# MCU.net
KiCad netlist of a schematic drawn in Altium Designer
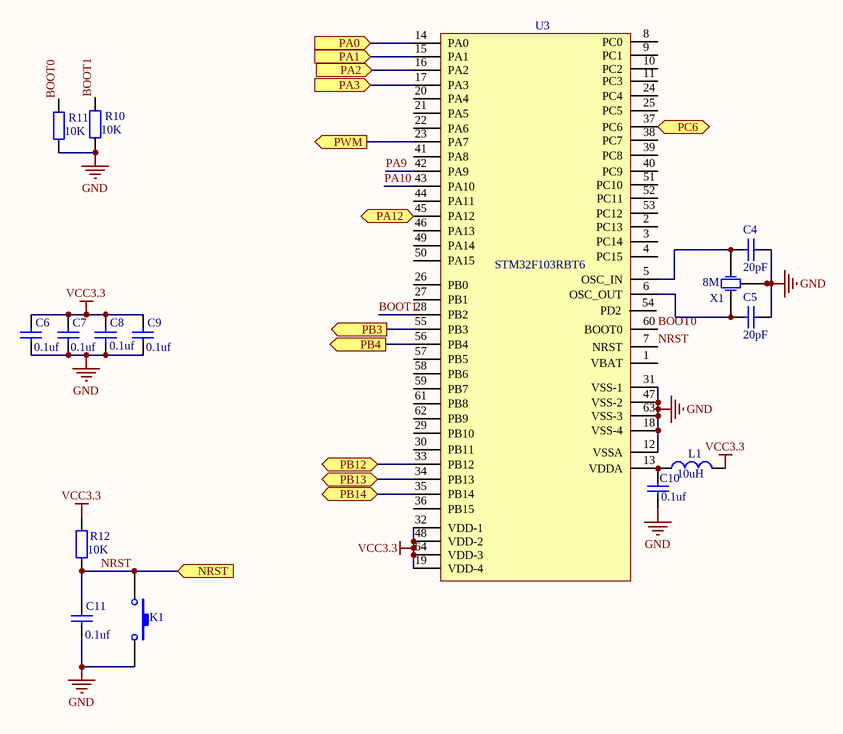
[diagram p0: MCU.SchDoc]

(export (version "E")
  (design (tool "Eeschema 10.0.6"))
  (components
    (comp (ref "C4")
      (value "20pF")
      (footprint "0603")
      (fields (field (name "Comment") "Capacitor-0805"))
      (libsource (lib "原理图库") (part "Capacitor-0805"))
    )
    (comp (ref "C5")
      (value "20pF")
      (footprint "0603")
      (fields (field (name "Comment") "Capacitor-0805"))
      (libsource (lib "原理图库") (part "Capacitor-0805"))
    )
    (comp (ref "C6")
      (value "0.1uf")
      (footprint "0603")
      (fields (field (name "Comment") "Capacitor-0603"))
      (libsource (lib "原理图库") (part "Capacitor-0603"))
    )
    (comp (ref "C7")
      (value "0.1uf")
      (footprint "0603")
      (fields (field (name "Comment") "Capacitor-0603"))
      (libsource (lib "原理图库") (part "Capacitor-0603"))
    )
    (comp (ref "C8")
      (value "0.1uf")
      (footprint "0603")
      (fields (field (name "Comment") "Capacitor-0603"))
      (libsource (lib "原理图库") (part "Capacitor-0603"))
    )
    (comp (ref "C9")
      (value "0.1uf")
      (footprint "0603")
      (fields (field (name "Comment") "Capacitor-0603"))
      (libsource (lib "原理图库") (part "Capacitor-0603"))
    )
    (comp (ref "C10")
      (value "0.1uf")
      (footprint "0603")
      (fields (field (name "Comment") "Capacitor-0603"))
      (libsource (lib "原理图库") (part "Capacitor-0603"))
    )
    (comp (ref "C11")
      (value "0.1uf")
      (footprint "0603")
      (fields (field (name "Comment") "Capacitor-0603"))
      (libsource (lib "原理图库") (part "Capacitor-0603"))
    )
    (comp (ref "K1") (value "按键") (footprint "mini按键") (libsource (lib "原理图库") (part "按键")))
    (comp (ref "L1")
      (value "10uH")
      (footprint "0805")
      (fields (field (name "Comment") "Inductor"))
      (libsource (lib "原理图库") (part "Inductor"))
    )
    (comp (ref "R10")
      (value "10K")
      (footprint "0603")
      (fields (field (name "Comment") "Resistor-0603"))
      (libsource (lib "原理图库") (part "Resistor-0603"))
    )
    (comp (ref "R11")
      (value "10K")
      (footprint "0603")
      (fields (field (name "Comment") "Resistor-0603"))
      (libsource (lib "原理图库") (part "Resistor-0603"))
    )
    (comp (ref "R12")
      (value "10K")
      (footprint "0603")
      (fields (field (name "Comment") "Resistor-0603"))
      (libsource (lib "原理图库") (part "Resistor-0603"))
    )
    (comp (ref "U3")
      (value "STM32F103RBT6")
      (footprint "STM32F103RBT6")
      (fields (field (name "NAME") "STM32F103RBT6"))
      (libsource (lib "原理图库") (part "STM32F103RBT6"))
    )
    (comp (ref "X1")
      (value "8M")
      (footprint "3225无源晶振")
      (fields (field (name "Comment") "3225无源晶振"))
      (libsource (lib "原理图库") (part "3225无源晶振"))
    )
  )
  (nets
    (net (code "1") (name "/BOOT0") (class "Default")
      (node (ref "R11") (pin "2") (pinfunction "2_2") (pintype "passive"))
      (node (ref "U3") (pin "60") (pinfunction "BOOT0_60") (pintype "passive"))
    )
    (net (code "2") (name "/BOOT1") (class "Default")
      (node (ref "R10") (pin "2") (pinfunction "2_2") (pintype "passive"))
      (node (ref "U3") (pin "28") (pinfunction "PB2_28") (pintype "passive"))
    )
    (net (code "3") (name "/NRST") (class "Default")
      (node (ref "C11") (pin "2") (pinfunction "2_2") (pintype "passive"))
      (node (ref "K1") (pin "1") (pinfunction "1_1") (pintype "passive"))
      (node (ref "R12") (pin "1") (pinfunction "1_1") (pintype "passive"))
      (node (ref "U3") (pin "7") (pinfunction "NRST_7") (pintype "passive"))
    )
    (net (code "4") (name "/PA0") (class "Default")
      (node (ref "U3") (pin "14") (pinfunction "PA0_14") (pintype "passive"))
    )
    (net (code "5") (name "/PA1") (class "Default")
      (node (ref "U3") (pin "15") (pinfunction "PA1_15") (pintype "passive"))
    )
    (net (code "6") (name "/PA2") (class "Default")
      (node (ref "U3") (pin "16") (pinfunction "PA2_16") (pintype "passive"))
    )
    (net (code "7") (name "/PA3") (class "Default")
      (node (ref "U3") (pin "17") (pinfunction "PA3_17") (pintype "passive"))
    )
    (net (code "8") (name "/PA9") (class "Default")
      (node (ref "U3") (pin "42") (pinfunction "PA9_42") (pintype "passive"))
    )
    (net (code "9") (name "/PA10") (class "Default")
      (node (ref "U3") (pin "43") (pinfunction "PA10_43") (pintype "passive"))
    )
    (net (code "10") (name "/PA12") (class "Default")
      (node (ref "U3") (pin "45") (pinfunction "PA12_45") (pintype "passive"))
    )
    (net (code "11") (name "/PB3") (class "Default")
      (node (ref "U3") (pin "55") (pinfunction "PB3_55") (pintype "passive"))
    )
    (net (code "12") (name "/PB4") (class "Default")
      (node (ref "U3") (pin "56") (pinfunction "PB4_56") (pintype "passive"))
    )
    (net (code "13") (name "/PB12") (class "Default")
      (node (ref "U3") (pin "33") (pinfunction "PB12_33") (pintype "passive"))
    )
    (net (code "14") (name "/PB13") (class "Default")
      (node (ref "U3") (pin "34") (pinfunction "PB13_34") (pintype "passive"))
    )
    (net (code "15") (name "/PB14") (class "Default")
      (node (ref "U3") (pin "35") (pinfunction "PB14_35") (pintype "passive"))
    )
    (net (code "16") (name "/PC6") (class "Default")
      (node (ref "U3") (pin "37") (pinfunction "PC6_37") (pintype "passive"))
    )
    (net (code "17") (name "/PWM") (class "Default")
      (node (ref "U3") (pin "23") (pinfunction "PA7_23") (pintype "passive"))
    )
    (net (code "18") (name "GND") (class "Default")
      (node (ref "C10") (pin "1") (pinfunction "1_1") (pintype "passive"))
      (node (ref "C11") (pin "1") (pinfunction "1_1") (pintype "passive"))
      (node (ref "C4") (pin "1") (pinfunction "1_1") (pintype "passive"))
      (node (ref "C5") (pin "1") (pinfunction "1_1") (pintype "passive"))
      (node (ref "C6") (pin "1") (pinfunction "1_1") (pintype "passive"))
      (node (ref "C7") (pin "1") (pinfunction "1_1") (pintype "passive"))
      (node (ref "C8") (pin "1") (pinfunction "1_1") (pintype "passive"))
      (node (ref "C9") (pin "1") (pinfunction "1_1") (pintype "passive"))
      (node (ref "K1") (pin "2") (pinfunction "2_2") (pintype "passive"))
      (node (ref "R10") (pin "1") (pinfunction "1_1") (pintype "passive"))
      (node (ref "R11") (pin "1") (pinfunction "1_1") (pintype "passive"))
      (node (ref "U3") (pin "12") (pinfunction "VSSA_12") (pintype "passive"))
      (node (ref "U3") (pin "18") (pinfunction "VSS-4_18") (pintype "passive"))
      (node (ref "U3") (pin "31") (pinfunction "VSS-1_31") (pintype "passive"))
      (node (ref "U3") (pin "47") (pinfunction "VSS-2_47") (pintype "passive"))
      (node (ref "U3") (pin "63") (pinfunction "VSS-3_63") (pintype "passive"))
      (node (ref "X1") (pin "2") (pinfunction "GND_2") (pintype "passive"))
      (node (ref "X1") (pin "4") (pinfunction "GND_4") (pintype "passive"))
    )
    (net (code "19") (name "Net-(U3-OSC_IN)") (class "Default")
      (node (ref "C4") (pin "2") (pinfunction "2_2") (pintype "passive"))
      (node (ref "U3") (pin "5") (pinfunction "OSC_IN_5") (pintype "passive"))
      (node (ref "X1") (pin "3") (pinfunction "OSC2_3") (pintype "passive"))
    )
    (net (code "20") (name "Net-(U3-OSC_OUT)") (class "Default")
      (node (ref "C5") (pin "2") (pinfunction "2_2") (pintype "passive"))
      (node (ref "U3") (pin "6") (pinfunction "OSC_OUT_6") (pintype "passive"))
      (node (ref "X1") (pin "1") (pinfunction "OSC1_1") (pintype "passive"))
    )
    (net (code "21") (name "Net-(U3-VDDA)") (class "Default")
      (node (ref "C10") (pin "2") (pinfunction "2_2") (pintype "passive"))
      (node (ref "L1") (pin "1") (pinfunction "1_1") (pintype "passive"))
      (node (ref "U3") (pin "13") (pinfunction "VDDA_13") (pintype "passive"))
    )
    (net (code "22") (name "VCC3.3") (class "Default")
      (node (ref "C6") (pin "2") (pinfunction "2_2") (pintype "passive"))
      (node (ref "C7") (pin "2") (pinfunction "2_2") (pintype "passive"))
      (node (ref "C8") (pin "2") (pinfunction "2_2") (pintype "passive"))
      (node (ref "C9") (pin "2") (pinfunction "2_2") (pintype "passive"))
      (node (ref "L1") (pin "2") (pinfunction "2_2") (pintype "passive"))
      (node (ref "R12") (pin "2") (pinfunction "2_2") (pintype "passive"))
      (node (ref "U3") (pin "19") (pinfunction "VDD-4_19") (pintype "passive"))
      (node (ref "U3") (pin "32") (pinfunction "VDD-1_32") (pintype "passive"))
      (node (ref "U3") (pin "48") (pinfunction "VDD-2_48") (pintype "passive"))
      (node (ref "U3") (pin "64") (pinfunction "VDD-3_64") (pintype "passive"))
    )
    (net (code "23") (name "unconnected-(U3-PA4-Pad20)") (class "Default")
      (node (ref "U3") (pin "20") (pinfunction "PA4_20") (pintype "passive"))
    )
    (net (code "24") (name "unconnected-(U3-PA5-Pad21)") (class "Default")
      (node (ref "U3") (pin "21") (pinfunction "PA5_21") (pintype "passive"))
    )
    (net (code "25") (name "unconnected-(U3-PA6-Pad22)") (class "Default")
      (node (ref "U3") (pin "22") (pinfunction "PA6_22") (pintype "passive"))
    )
    (net (code "26") (name "unconnected-(U3-PA8-Pad41)") (class "Default")
      (node (ref "U3") (pin "41") (pinfunction "PA8_41") (pintype "passive"))
    )
    (net (code "27") (name "unconnected-(U3-PA11-Pad44)") (class "Default")
      (node (ref "U3") (pin "44") (pinfunction "PA11_44") (pintype "passive"))
    )
    (net (code "28") (name "unconnected-(U3-PA13-Pad46)") (class "Default")
      (node (ref "U3") (pin "46") (pinfunction "PA13_46") (pintype "passive"))
    )
    (net (code "29") (name "unconnected-(U3-PA14-Pad49)") (class "Default")
      (node (ref "U3") (pin "49") (pinfunction "PA14_49") (pintype "passive"))
    )
    (net (code "30") (name "unconnected-(U3-PA15-Pad50)") (class "Default")
      (node (ref "U3") (pin "50") (pinfunction "PA15_50") (pintype "passive"))
    )
    (net (code "31") (name "unconnected-(U3-PB0-Pad26)") (class "Default")
      (node (ref "U3") (pin "26") (pinfunction "PB0_26") (pintype "passive"))
    )
    (net (code "32") (name "unconnected-(U3-PB1-Pad27)") (class "Default")
      (node (ref "U3") (pin "27") (pinfunction "PB1_27") (pintype "passive"))
    )
    (net (code "33") (name "unconnected-(U3-PB5-Pad57)") (class "Default")
      (node (ref "U3") (pin "57") (pinfunction "PB5_57") (pintype "passive"))
    )
    (net (code "34") (name "unconnected-(U3-PB6-Pad58)") (class "Default")
      (node (ref "U3") (pin "58") (pinfunction "PB6_58") (pintype "passive"))
    )
    (net (code "35") (name "unconnected-(U3-PB7-Pad59)") (class "Default")
      (node (ref "U3") (pin "59") (pinfunction "PB7_59") (pintype "passive"))
    )
    (net (code "36") (name "unconnected-(U3-PB8-Pad61)") (class "Default")
      (node (ref "U3") (pin "61") (pinfunction "PB8_61") (pintype "passive"))
    )
    (net (code "37") (name "unconnected-(U3-PB9-Pad62)") (class "Default")
      (node (ref "U3") (pin "62") (pinfunction "PB9_62") (pintype "passive"))
    )
    (net (code "38") (name "unconnected-(U3-PB10-Pad29)") (class "Default")
      (node (ref "U3") (pin "29") (pinfunction "PB10_29") (pintype "passive"))
    )
    (net (code "39") (name "unconnected-(U3-PB11-Pad30)") (class "Default")
      (node (ref "U3") (pin "30") (pinfunction "PB11_30") (pintype "passive"))
    )
    (net (code "40") (name "unconnected-(U3-PB15-Pad36)") (class "Default")
      (node (ref "U3") (pin "36") (pinfunction "PB15_36") (pintype "passive"))
    )
    (net (code "41") (name "unconnected-(U3-PC0-Pad8)") (class "Default")
      (node (ref "U3") (pin "8") (pinfunction "PC0_8") (pintype "passive"))
    )
    (net (code "42") (name "unconnected-(U3-PC1-Pad9)") (class "Default")
      (node (ref "U3") (pin "9") (pinfunction "PC1_9") (pintype "passive"))
    )
    (net (code "43") (name "unconnected-(U3-PC2-Pad10)") (class "Default")
      (node (ref "U3") (pin "10") (pinfunction "PC2_10") (pintype "passive"))
    )
    (net (code "44") (name "unconnected-(U3-PC3-Pad11)") (class "Default")
      (node (ref "U3") (pin "11") (pinfunction "PC3_11") (pintype "passive"))
    )
    (net (code "45") (name "unconnected-(U3-PC4-Pad24)") (class "Default")
      (node (ref "U3") (pin "24") (pinfunction "PC4_24") (pintype "passive"))
    )
    (net (code "46") (name "unconnected-(U3-PC5-Pad25)") (class "Default")
      (node (ref "U3") (pin "25") (pinfunction "PC5_25") (pintype "passive"))
    )
    (net (code "47") (name "unconnected-(U3-PC7-Pad38)") (class "Default")
      (node (ref "U3") (pin "38") (pinfunction "PC7_38") (pintype "passive"))
    )
    (net (code "48") (name "unconnected-(U3-PC8-Pad39)") (class "Default")
      (node (ref "U3") (pin "39") (pinfunction "PC8_39") (pintype "passive"))
    )
    (net (code "49") (name "unconnected-(U3-PC9-Pad40)") (class "Default")
      (node (ref "U3") (pin "40") (pinfunction "PC9_40") (pintype "passive"))
    )
    (net (code "50") (name "unconnected-(U3-PC10-Pad51)") (class "Default")
      (node (ref "U3") (pin "51") (pinfunction "PC10_51") (pintype "passive"))
    )
    (net (code "51") (name "unconnected-(U3-PC11-Pad52)") (class "Default")
      (node (ref "U3") (pin "52") (pinfunction "PC11_52") (pintype "passive"))
    )
    (net (code "52") (name "unconnected-(U3-PC12-Pad53)") (class "Default")
      (node (ref "U3") (pin "53") (pinfunction "PC12_53") (pintype "passive"))
    )
    (net (code "53") (name "unconnected-(U3-PC13-Pad2)") (class "Default")
      (node (ref "U3") (pin "2") (pinfunction "PC13_2") (pintype "passive"))
    )
    (net (code "54") (name "unconnected-(U3-PC14-Pad3)") (class "Default")
      (node (ref "U3") (pin "3") (pinfunction "PC14_3") (pintype "passive"))
    )
    (net (code "55") (name "unconnected-(U3-PC15-Pad4)") (class "Default")
      (node (ref "U3") (pin "4") (pinfunction "PC15_4") (pintype "passive"))
    )
    (net (code "56") (name "unconnected-(U3-PD2-Pad54)") (class "Default")
      (node (ref "U3") (pin "54") (pinfunction "PD2_54") (pintype "passive"))
    )
    (net (code "57") (name "unconnected-(U3-VBAT-Pad1)") (class "Default")
      (node (ref "U3") (pin "1") (pinfunction "VBAT_1") (pintype "passive"))
    )
  )
)
